# LB_BIT_i13_LIGHTSENSOR-v02_rev1_01.net
KiCad netlist of a schematic drawn in EAGLE
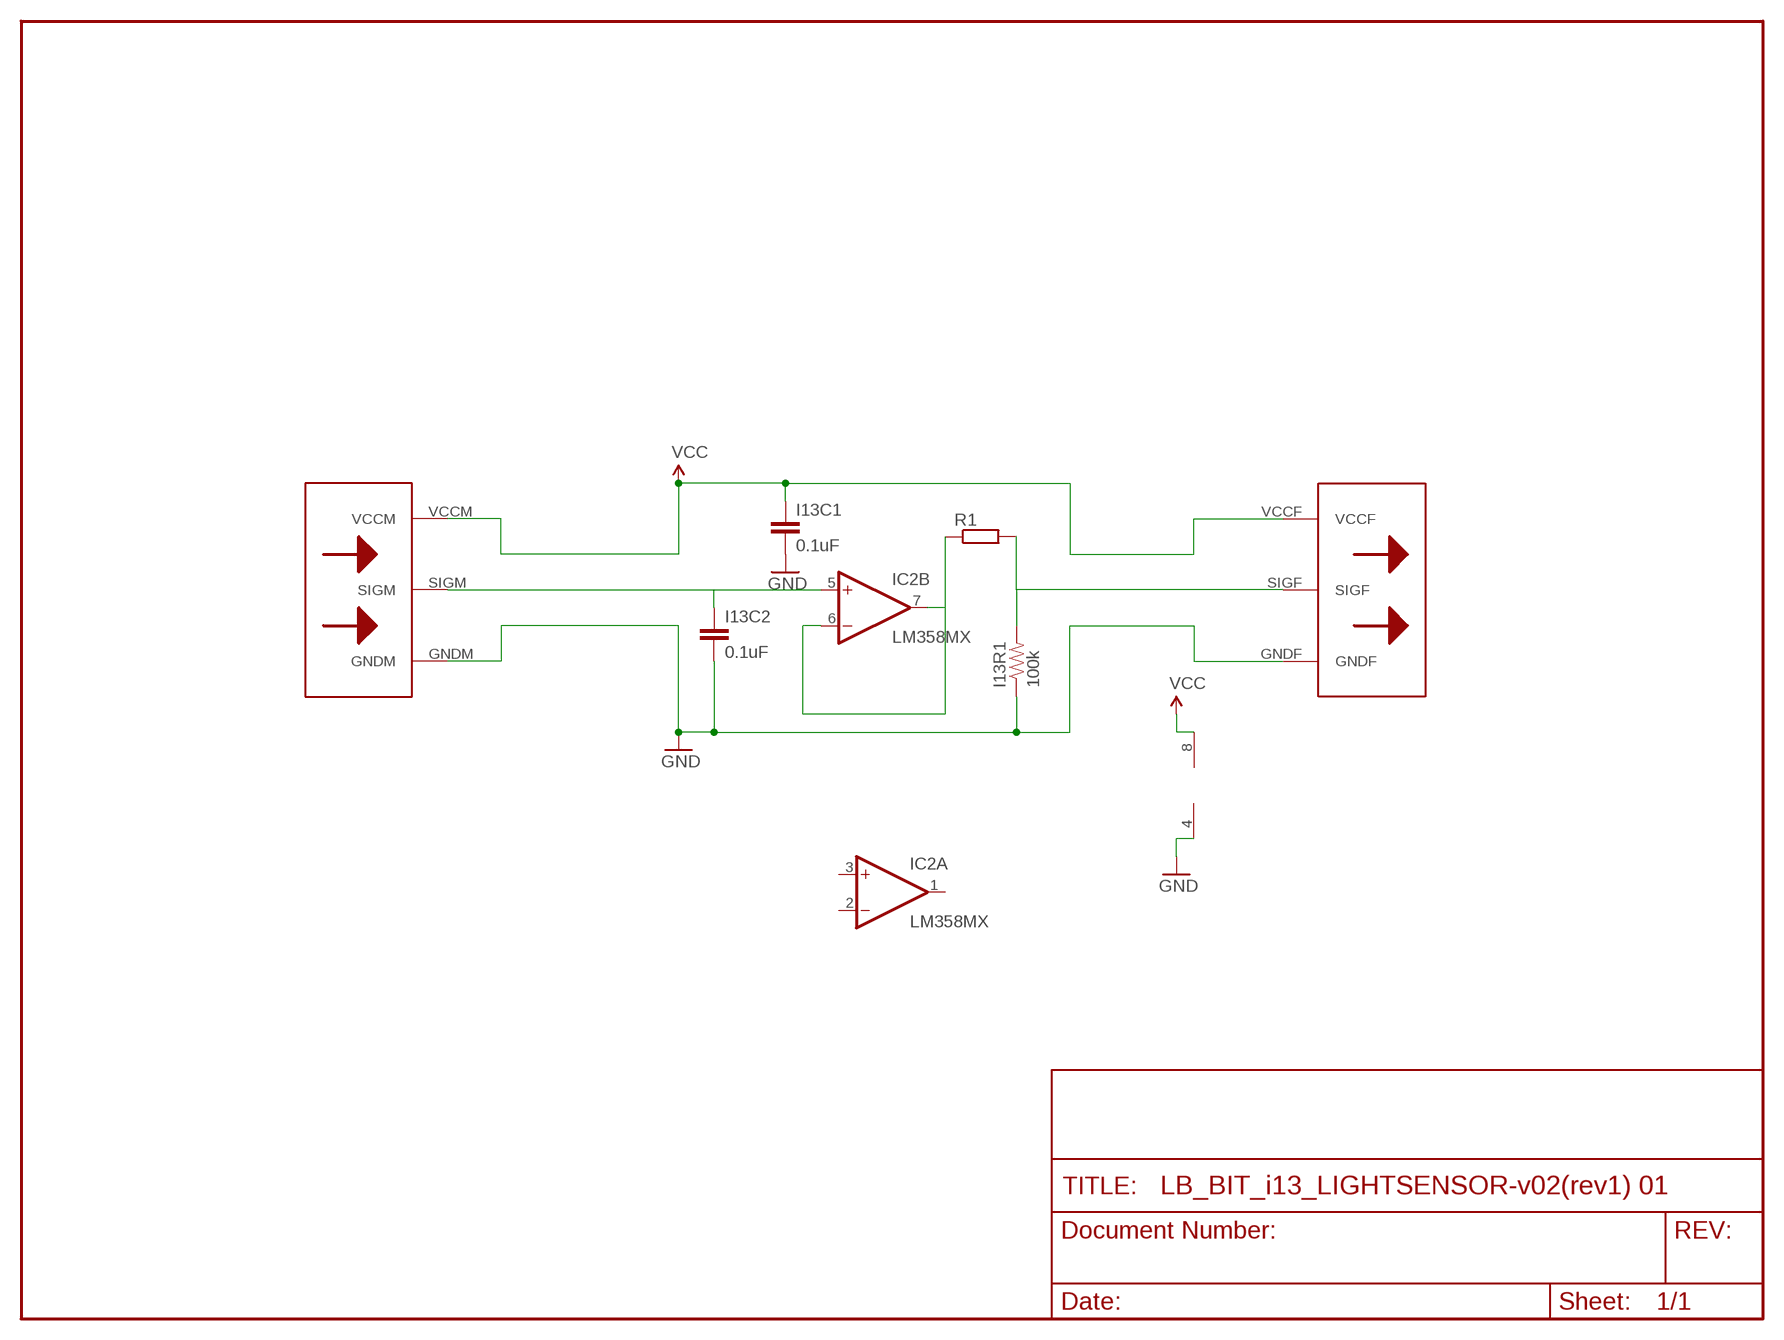
[diagram p0: schematic, sheet 1]

(export (version "E")
  (design (tool "Eeschema 10.0.6"))
  (components
    (comp (ref "I13C1")
      (value "0.1uF")
      (footprint "eagle-import:1206")
      (libsource (lib "eagle-import") (part "CAP1206"))
    )
    (comp (ref "I13C2")
      (value "0.1uF")
      (footprint "eagle-import:1206")
      (libsource (lib "eagle-import") (part "CAP1206"))
    )
    (comp (ref "I13R1")
      (value "100k")
      (footprint "eagle-import:0805")
      (libsource (lib "eagle-import") (part "RESISTOR0805-RES"))
    )
    (comp (ref "IC2")
      (value "LM358MX")
      (footprint "eagle-import:SO08")
      (libsource (lib "eagle-import") (part "LM358MX"))
    )
    (comp (ref "R1")
      (value "R-EU_R2512")
      (footprint "eagle-import:R2512")
      (libsource (lib "eagle-import") (part "R-EU_R2512"))
    )
    (comp (ref "U$1")
      (value "BIGBIT")
      (footprint "eagle-import:BIGBIT")
      (libsource (lib "eagle-import") (part "BIGBIT"))
    )
  )
  (nets
    (net (code "1") (name "GND") (class "Default")
      (node (ref "I13C1") (pin "2") (pinfunction "2_2") (pintype "passive"))
      (node (ref "I13C2") (pin "2") (pinfunction "2_2") (pintype "passive"))
      (node (ref "I13R1") (pin "1") (pinfunction "1_1") (pintype "passive"))
      (node (ref "IC2") (pin "4") (pinfunction "V-_4") (pintype "power_in"))
      (node (ref "U$1") (pin "GNDF") (pinfunction "GNDF_GNDF") (pintype "bidirectional"))
      (node (ref "U$1") (pin "GNDM") (pinfunction "GNDM_GNDM") (pintype "bidirectional"))
    )
    (net (code "2") (name "Net-(I13R1-Pad2)") (class "Default")
      (node (ref "I13R1") (pin "2") (pinfunction "2_2") (pintype "passive"))
      (node (ref "R1") (pin "2") (pinfunction "2_2") (pintype "passive"))
      (node (ref "U$1") (pin "SIGF") (pinfunction "SIGF_SIGF") (pintype "bidirectional"))
    )
    (net (code "3") (name "Net-(IC2B-+IN)") (class "Default")
      (node (ref "I13C2") (pin "1") (pinfunction "1_1") (pintype "passive"))
      (node (ref "IC2") (pin "5") (pinfunction "+IN_5") (pintype "input"))
      (node (ref "U$1") (pin "SIGM") (pinfunction "SIGM_SIGM") (pintype "bidirectional"))
    )
    (net (code "4") (name "Net-(IC2B--IN)") (class "Default")
      (node (ref "IC2") (pin "6") (pinfunction "-IN_6") (pintype "input"))
      (node (ref "IC2") (pin "7") (pinfunction "OUT_7") (pintype "output"))
      (node (ref "R1") (pin "1") (pinfunction "1_1") (pintype "passive"))
    )
    (net (code "5") (name "VCC") (class "Default")
      (node (ref "I13C1") (pin "1") (pinfunction "1_1") (pintype "passive"))
      (node (ref "IC2") (pin "8") (pinfunction "V+_8") (pintype "power_in"))
      (node (ref "U$1") (pin "VCCF") (pinfunction "VCCF_VCCF") (pintype "bidirectional"))
      (node (ref "U$1") (pin "VCCM") (pinfunction "VCCM_VCCM") (pintype "bidirectional"))
    )
    (net (code "6") (name "unconnected-(IC2A-+IN-Pad3)") (class "Default")
      (node (ref "IC2") (pin "3") (pinfunction "+IN_3") (pintype "input"))
    )
    (net (code "7") (name "unconnected-(IC2A--IN-Pad2)") (class "Default")
      (node (ref "IC2") (pin "2") (pinfunction "-IN_2") (pintype "input"))
    )
    (net (code "8") (name "unconnected-(IC2A-OUT-Pad1)") (class "Default")
      (node (ref "IC2") (pin "1") (pinfunction "OUT_1") (pintype "output"))
    )
  )
)
